# L003-ShiftRegister_-_Schematic.net
KiCad netlist of a schematic drawn in EAGLE
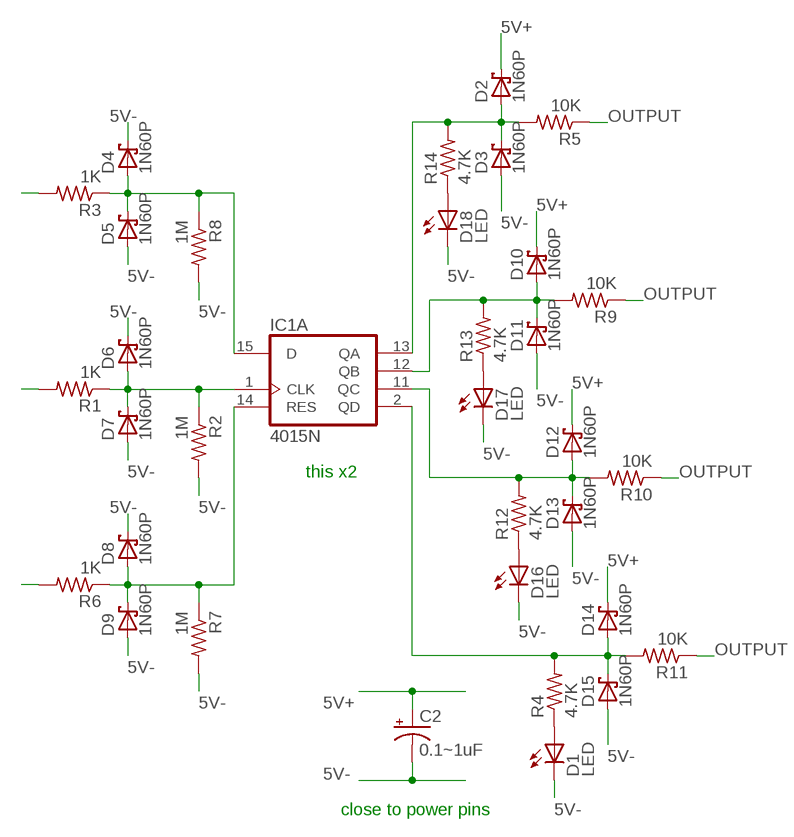
[diagram p0: schematic, sheet 1]

(export (version "E")
  (design (tool "Eeschema 10.0.6"))
  (components
    (comp (ref "C2")
      (value "0.1~1uF")
      (footprint "eagle-import:E2,5-6")
      (libsource (lib "eagle-import") (part "CPOL-USE2.5-6"))
    )
    (comp (ref "D1")
      (value "LED")
      (footprint "eagle-import:SFH482")
      (libsource (lib "eagle-import") (part "SFH482"))
    )
    (comp (ref "D2")
      (value "1N60P")
      (footprint "eagle-import:DO41-7.6")
      (libsource (lib "eagle-import") (part "1N5817-B"))
    )
    (comp (ref "D3")
      (value "1N60P")
      (footprint "eagle-import:DO41-7.6")
      (libsource (lib "eagle-import") (part "1N5817-B"))
    )
    (comp (ref "D4")
      (value "1N60P")
      (footprint "eagle-import:DO41-7.6")
      (libsource (lib "eagle-import") (part "1N5817-B"))
    )
    (comp (ref "D5")
      (value "1N60P")
      (footprint "eagle-import:DO41-7.6")
      (libsource (lib "eagle-import") (part "1N5817-B"))
    )
    (comp (ref "D6")
      (value "1N60P")
      (footprint "eagle-import:DO41-7.6")
      (libsource (lib "eagle-import") (part "1N5817-B"))
    )
    (comp (ref "D7")
      (value "1N60P")
      (footprint "eagle-import:DO41-7.6")
      (libsource (lib "eagle-import") (part "1N5817-B"))
    )
    (comp (ref "D8")
      (value "1N60P")
      (footprint "eagle-import:DO41-7.6")
      (libsource (lib "eagle-import") (part "1N5817-B"))
    )
    (comp (ref "D9")
      (value "1N60P")
      (footprint "eagle-import:DO41-7.6")
      (libsource (lib "eagle-import") (part "1N5817-B"))
    )
    (comp (ref "D10")
      (value "1N60P")
      (footprint "eagle-import:DO41-7.6")
      (libsource (lib "eagle-import") (part "1N5817-B"))
    )
    (comp (ref "D11")
      (value "1N60P")
      (footprint "eagle-import:DO41-7.6")
      (libsource (lib "eagle-import") (part "1N5817-B"))
    )
    (comp (ref "D12")
      (value "1N60P")
      (footprint "eagle-import:DO41-7.6")
      (libsource (lib "eagle-import") (part "1N5817-B"))
    )
    (comp (ref "D13")
      (value "1N60P")
      (footprint "eagle-import:DO41-7.6")
      (libsource (lib "eagle-import") (part "1N5817-B"))
    )
    (comp (ref "D14")
      (value "1N60P")
      (footprint "eagle-import:DO41-7.6")
      (libsource (lib "eagle-import") (part "1N5817-B"))
    )
    (comp (ref "D15")
      (value "1N60P")
      (footprint "eagle-import:DO41-7.6")
      (libsource (lib "eagle-import") (part "1N5817-B"))
    )
    (comp (ref "D16")
      (value "LED")
      (footprint "eagle-import:SFH482")
      (libsource (lib "eagle-import") (part "SFH482"))
    )
    (comp (ref "D17")
      (value "LED")
      (footprint "eagle-import:SFH482")
      (libsource (lib "eagle-import") (part "SFH482"))
    )
    (comp (ref "D18")
      (value "LED")
      (footprint "eagle-import:SFH482")
      (libsource (lib "eagle-import") (part "SFH482"))
    )
    (comp (ref "IC1")
      (value "4015N")
      (footprint "eagle-import:DIL16")
      (libsource (lib "eagle-import") (part "4015N"))
    )
    (comp (ref "R1")
      (value "1K")
      (footprint "eagle-import:VMTA55")
      (libsource (lib "eagle-import") (part "R-US_VMTA55"))
    )
    (comp (ref "R2")
      (value "1M")
      (footprint "eagle-import:VMTA55")
      (libsource (lib "eagle-import") (part "R-US_VMTA55"))
    )
    (comp (ref "R3")
      (value "1K")
      (footprint "eagle-import:VMTA55")
      (libsource (lib "eagle-import") (part "R-US_VMTA55"))
    )
    (comp (ref "R4")
      (value "4.7K")
      (footprint "eagle-import:VMTA55")
      (libsource (lib "eagle-import") (part "R-US_VMTA55"))
    )
    (comp (ref "R5")
      (value "10K")
      (footprint "eagle-import:VMTA55")
      (libsource (lib "eagle-import") (part "R-US_VMTA55"))
    )
    (comp (ref "R6")
      (value "1K")
      (footprint "eagle-import:VMTA55")
      (libsource (lib "eagle-import") (part "R-US_VMTA55"))
    )
    (comp (ref "R7")
      (value "1M")
      (footprint "eagle-import:VMTA55")
      (libsource (lib "eagle-import") (part "R-US_VMTA55"))
    )
    (comp (ref "R8")
      (value "1M")
      (footprint "eagle-import:VMTA55")
      (libsource (lib "eagle-import") (part "R-US_VMTA55"))
    )
    (comp (ref "R9")
      (value "10K")
      (footprint "eagle-import:VMTA55")
      (libsource (lib "eagle-import") (part "R-US_VMTA55"))
    )
    (comp (ref "R10")
      (value "10K")
      (footprint "eagle-import:VMTA55")
      (libsource (lib "eagle-import") (part "R-US_VMTA55"))
    )
    (comp (ref "R11")
      (value "10K")
      (footprint "eagle-import:VMTA55")
      (libsource (lib "eagle-import") (part "R-US_VMTA55"))
    )
    (comp (ref "R12")
      (value "4.7K")
      (footprint "eagle-import:VMTA55")
      (libsource (lib "eagle-import") (part "R-US_VMTA55"))
    )
    (comp (ref "R13")
      (value "4.7K")
      (footprint "eagle-import:VMTA55")
      (libsource (lib "eagle-import") (part "R-US_VMTA55"))
    )
    (comp (ref "R14")
      (value "4.7K")
      (footprint "eagle-import:VMTA55")
      (libsource (lib "eagle-import") (part "R-US_VMTA55"))
    )
  )
  (nets
    (net (code "1") (name "/5V+") (class "Default")
      (node (ref "C2") (pin "+") (pinfunction "+_+") (pintype "passive"))
      (node (ref "D10") (pin "C") (pinfunction "C_C") (pintype "passive"))
      (node (ref "D12") (pin "C") (pinfunction "C_C") (pintype "passive"))
      (node (ref "D14") (pin "C") (pinfunction "C_C") (pintype "passive"))
      (node (ref "D2") (pin "C") (pinfunction "C_C") (pintype "passive"))
    )
    (net (code "2") (name "/5V-") (class "Default")
      (node (ref "C2") (pin "-") (pinfunction "-_-") (pintype "passive"))
      (node (ref "D1") (pin "K") (pinfunction "C_K") (pintype "passive"))
      (node (ref "D11") (pin "A") (pinfunction "A_A") (pintype "passive"))
      (node (ref "D13") (pin "A") (pinfunction "A_A") (pintype "passive"))
      (node (ref "D15") (pin "A") (pinfunction "A_A") (pintype "passive"))
      (node (ref "D16") (pin "K") (pinfunction "C_K") (pintype "passive"))
      (node (ref "D17") (pin "K") (pinfunction "C_K") (pintype "passive"))
      (node (ref "D18") (pin "K") (pinfunction "C_K") (pintype "passive"))
      (node (ref "D3") (pin "A") (pinfunction "A_A") (pintype "passive"))
      (node (ref "D4") (pin "C") (pinfunction "C_C") (pintype "passive"))
      (node (ref "D5") (pin "A") (pinfunction "A_A") (pintype "passive"))
      (node (ref "D6") (pin "C") (pinfunction "C_C") (pintype "passive"))
      (node (ref "D7") (pin "A") (pinfunction "A_A") (pintype "passive"))
      (node (ref "D8") (pin "C") (pinfunction "C_C") (pintype "passive"))
      (node (ref "D9") (pin "A") (pinfunction "A_A") (pintype "passive"))
      (node (ref "R2") (pin "2") (pinfunction "2_2") (pintype "passive"))
      (node (ref "R7") (pin "2") (pinfunction "2_2") (pintype "passive"))
      (node (ref "R8") (pin "2") (pinfunction "2_2") (pintype "passive"))
    )
    (net (code "3") (name "/OUTPUT") (class "Default")
      (node (ref "R10") (pin "1") (pinfunction "1_1") (pintype "passive"))
      (node (ref "R11") (pin "1") (pinfunction "1_1") (pintype "passive"))
      (node (ref "R5") (pin "1") (pinfunction "1_1") (pintype "passive"))
      (node (ref "R9") (pin "1") (pinfunction "1_1") (pintype "passive"))
    )
    (net (code "4") (name "Net-(D1-PadA)") (class "Default")
      (node (ref "D1") (pin "A") (pinfunction "A_A") (pintype "passive"))
      (node (ref "R4") (pin "1") (pinfunction "1_1") (pintype "passive"))
    )
    (net (code "5") (name "Net-(D16-PadA)") (class "Default")
      (node (ref "D16") (pin "A") (pinfunction "A_A") (pintype "passive"))
      (node (ref "R12") (pin "1") (pinfunction "1_1") (pintype "passive"))
    )
    (net (code "6") (name "Net-(D17-PadA)") (class "Default")
      (node (ref "D17") (pin "A") (pinfunction "A_A") (pintype "passive"))
      (node (ref "R13") (pin "1") (pinfunction "1_1") (pintype "passive"))
    )
    (net (code "7") (name "Net-(D18-PadA)") (class "Default")
      (node (ref "D18") (pin "A") (pinfunction "A_A") (pintype "passive"))
      (node (ref "R14") (pin "1") (pinfunction "1_1") (pintype "passive"))
    )
    (net (code "8") (name "Net-(IC1A-CLK)") (class "Default")
      (node (ref "D6") (pin "A") (pinfunction "A_A") (pintype "passive"))
      (node (ref "D7") (pin "C") (pinfunction "C_C") (pintype "passive"))
      (node (ref "IC1") (pin "1") (pinfunction "CLK_1") (pintype "input"))
      (node (ref "R1") (pin "1") (pinfunction "1_1") (pintype "passive"))
      (node (ref "R2") (pin "1") (pinfunction "1_1") (pintype "passive"))
    )
    (net (code "9") (name "Net-(IC1A-D)") (class "Default")
      (node (ref "D4") (pin "A") (pinfunction "A_A") (pintype "passive"))
      (node (ref "D5") (pin "C") (pinfunction "C_C") (pintype "passive"))
      (node (ref "IC1") (pin "15") (pinfunction "D_15") (pintype "input"))
      (node (ref "R3") (pin "1") (pinfunction "1_1") (pintype "passive"))
      (node (ref "R8") (pin "1") (pinfunction "1_1") (pintype "passive"))
    )
    (net (code "10") (name "Net-(IC1A-QA)") (class "Default")
      (node (ref "D2") (pin "A") (pinfunction "A_A") (pintype "passive"))
      (node (ref "D3") (pin "C") (pinfunction "C_C") (pintype "passive"))
      (node (ref "IC1") (pin "13") (pinfunction "QA_13") (pintype "output"))
      (node (ref "R14") (pin "2") (pinfunction "2_2") (pintype "passive"))
      (node (ref "R5") (pin "2") (pinfunction "2_2") (pintype "passive"))
    )
    (net (code "11") (name "Net-(IC1A-QB)") (class "Default")
      (node (ref "D10") (pin "A") (pinfunction "A_A") (pintype "passive"))
      (node (ref "D11") (pin "C") (pinfunction "C_C") (pintype "passive"))
      (node (ref "IC1") (pin "12") (pinfunction "QB_12") (pintype "output"))
      (node (ref "R13") (pin "2") (pinfunction "2_2") (pintype "passive"))
      (node (ref "R9") (pin "2") (pinfunction "2_2") (pintype "passive"))
    )
    (net (code "12") (name "Net-(IC1A-QC)") (class "Default")
      (node (ref "D12") (pin "A") (pinfunction "A_A") (pintype "passive"))
      (node (ref "D13") (pin "C") (pinfunction "C_C") (pintype "passive"))
      (node (ref "IC1") (pin "11") (pinfunction "QC_11") (pintype "output"))
      (node (ref "R10") (pin "2") (pinfunction "2_2") (pintype "passive"))
      (node (ref "R12") (pin "2") (pinfunction "2_2") (pintype "passive"))
    )
    (net (code "13") (name "Net-(IC1A-QD)") (class "Default")
      (node (ref "D14") (pin "A") (pinfunction "A_A") (pintype "passive"))
      (node (ref "D15") (pin "C") (pinfunction "C_C") (pintype "passive"))
      (node (ref "IC1") (pin "2") (pinfunction "QD_2") (pintype "output"))
      (node (ref "R11") (pin "2") (pinfunction "2_2") (pintype "passive"))
      (node (ref "R4") (pin "2") (pinfunction "2_2") (pintype "passive"))
    )
    (net (code "14") (name "Net-(IC1A-RES)") (class "Default")
      (node (ref "D8") (pin "A") (pinfunction "A_A") (pintype "passive"))
      (node (ref "D9") (pin "C") (pinfunction "C_C") (pintype "passive"))
      (node (ref "IC1") (pin "14") (pinfunction "RES_14") (pintype "input"))
      (node (ref "R6") (pin "1") (pinfunction "1_1") (pintype "passive"))
      (node (ref "R7") (pin "1") (pinfunction "1_1") (pintype "passive"))
    )
    (net (code "15") (name "unconnected-(R1-Pad2)") (class "Default")
      (node (ref "R1") (pin "2") (pinfunction "2_2") (pintype "passive"))
    )
    (net (code "16") (name "unconnected-(R3-Pad2)") (class "Default")
      (node (ref "R3") (pin "2") (pinfunction "2_2") (pintype "passive"))
    )
    (net (code "17") (name "unconnected-(R6-Pad2)") (class "Default")
      (node (ref "R6") (pin "2") (pinfunction "2_2") (pintype "passive"))
    )
  )
)
